# adc-breakout.net
KiCad netlist of a schematic drawn in Altium Designer
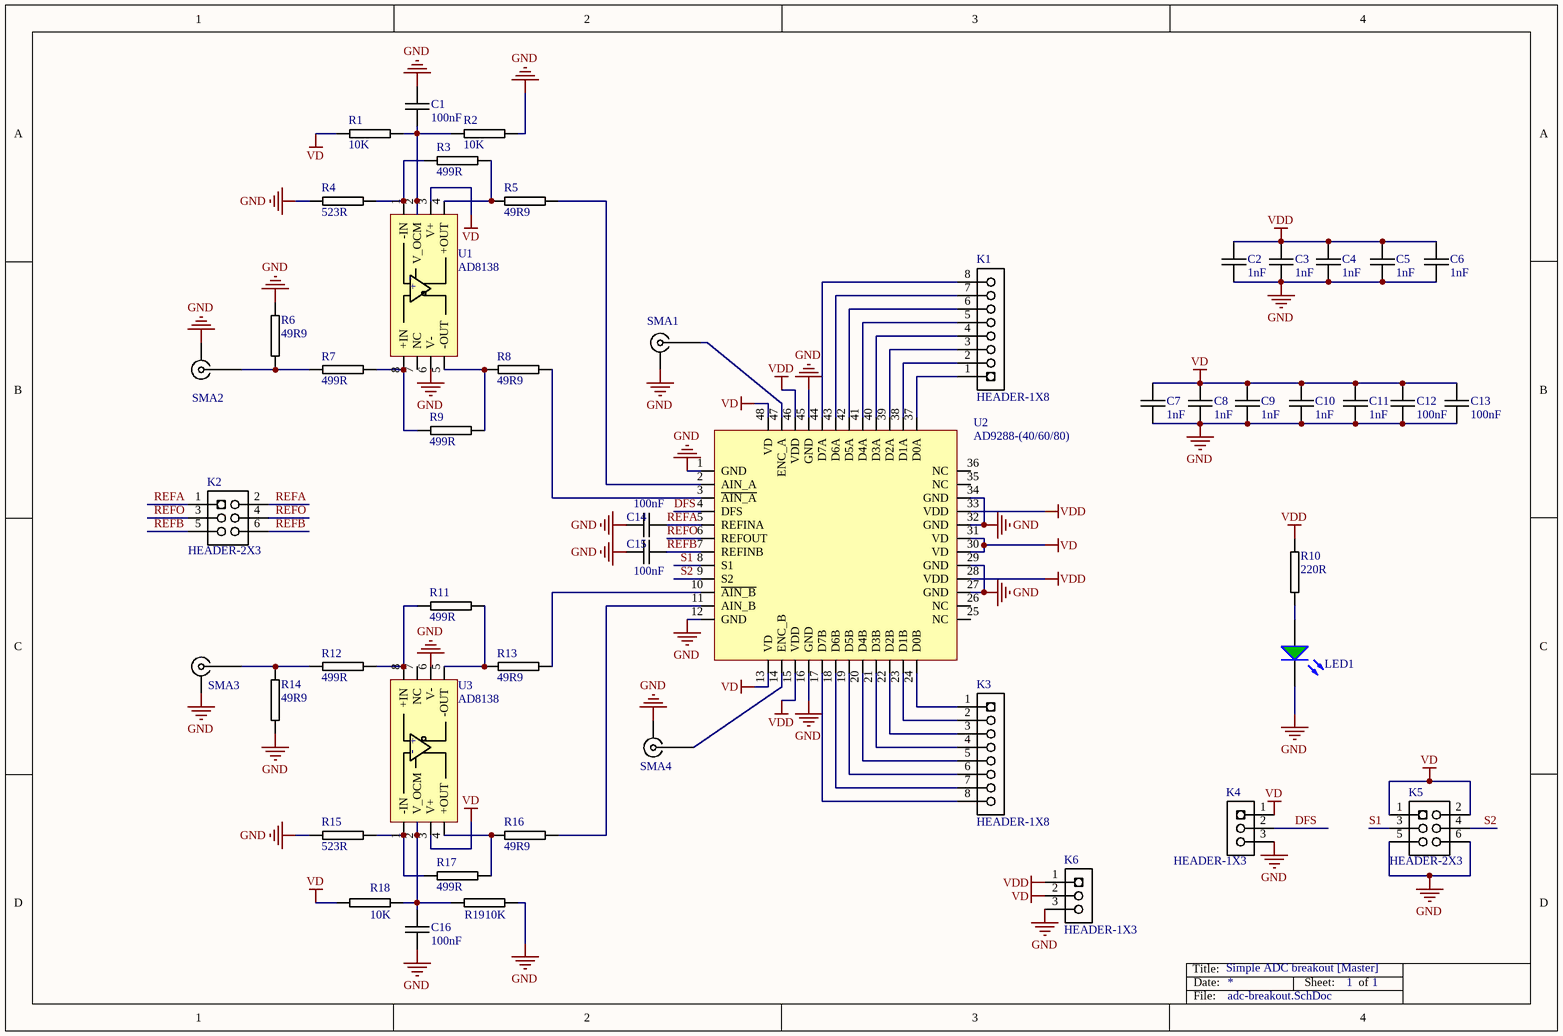
[diagram p0: adc-breakout.SchDoc]

(export (version "E")
  (design (tool "Eeschema 10.0.6"))
  (components
    (comp (ref "C1")
      (value "100nF")
      (footprint "0603C-GENERIC")
      (description "CAPACITOR 0603 CERAMIC")
      (fields
        (field (name "MANUFACTURER PART NUMBER") "C1608X7R1E104K")
        (field (name "MANUFACTURER") "TDK Corporation")
      )
      (libsource (lib "SMD Capacitors 0603") (part "0603C-100NF-25V-X7R-TDK"))
    )
    (comp (ref "C2")
      (value "1nF")
      (footprint "0603C-GENERIC")
      (description "CAPACITOR 0603 CERAMIC")
      (libsource (lib "SMD Capacitors 0603") (part "0603C-1NF-50V-X7R"))
    )
    (comp (ref "C3")
      (value "1nF")
      (footprint "0603C-GENERIC")
      (description "CAPACITOR 0603 CERAMIC")
      (libsource (lib "SMD Capacitors 0603") (part "0603C-1NF-50V-X7R"))
    )
    (comp (ref "C4")
      (value "1nF")
      (footprint "0603C-GENERIC")
      (description "CAPACITOR 0603 CERAMIC")
      (libsource (lib "SMD Capacitors 0603") (part "0603C-1NF-50V-X7R"))
    )
    (comp (ref "C5")
      (value "1nF")
      (footprint "0603C-GENERIC")
      (description "CAPACITOR 0603 CERAMIC")
      (libsource (lib "SMD Capacitors 0603") (part "0603C-1NF-50V-X7R"))
    )
    (comp (ref "C6")
      (value "1nF")
      (footprint "0603C-GENERIC")
      (description "CAPACITOR 0603 CERAMIC")
      (libsource (lib "SMD Capacitors 0603") (part "0603C-1NF-50V-X7R"))
    )
    (comp (ref "C7")
      (value "1nF")
      (footprint "0603C-GENERIC")
      (description "CAPACITOR 0603 CERAMIC")
      (libsource (lib "SMD Capacitors 0603") (part "0603C-1NF-50V-X7R"))
    )
    (comp (ref "C8")
      (value "1nF")
      (footprint "0603C-GENERIC")
      (description "CAPACITOR 0603 CERAMIC")
      (libsource (lib "SMD Capacitors 0603") (part "0603C-1NF-50V-X7R"))
    )
    (comp (ref "C9")
      (value "1nF")
      (footprint "0603C-GENERIC")
      (description "CAPACITOR 0603 CERAMIC")
      (libsource (lib "SMD Capacitors 0603") (part "0603C-1NF-50V-X7R"))
    )
    (comp (ref "C10")
      (value "1nF")
      (footprint "0603C-GENERIC")
      (description "CAPACITOR 0603 CERAMIC")
      (libsource (lib "SMD Capacitors 0603") (part "0603C-1NF-50V-X7R"))
    )
    (comp (ref "C11")
      (value "1nF")
      (footprint "0603C-GENERIC")
      (description "CAPACITOR 0603 CERAMIC")
      (libsource (lib "SMD Capacitors 0603") (part "0603C-1NF-50V-X7R"))
    )
    (comp (ref "C12")
      (value "100nF")
      (footprint "0603C-GENERIC")
      (description "CAPACITOR 0603 CERAMIC")
      (fields
        (field (name "MANUFACTURER PART NUMBER") "C1608X7R1E104K")
        (field (name "MANUFACTURER") "TDK Corporation")
      )
      (libsource (lib "SMD Capacitors 0603") (part "0603C-100NF-25V-X7R-TDK"))
    )
    (comp (ref "C13")
      (value "100nF")
      (footprint "0603C-GENERIC")
      (description "CAPACITOR 0603 CERAMIC")
      (fields
        (field (name "MANUFACTURER PART NUMBER") "C1608X7R1E104K")
        (field (name "MANUFACTURER") "TDK Corporation")
      )
      (libsource (lib "SMD Capacitors 0603") (part "0603C-100NF-25V-X7R-TDK"))
    )
    (comp (ref "C14")
      (value "100nF")
      (footprint "0603C-GENERIC")
      (description "CAPACITOR 0603 CERAMIC")
      (fields
        (field (name "MANUFACTURER PART NUMBER") "C1608X7R1E104K")
        (field (name "MANUFACTURER") "TDK Corporation")
      )
      (libsource (lib "SMD Capacitors 0603") (part "0603C-100NF-25V-X7R-TDK"))
    )
    (comp (ref "C15")
      (value "100nF")
      (footprint "0603C-GENERIC")
      (description "CAPACITOR 0603 CERAMIC")
      (fields
        (field (name "MANUFACTURER PART NUMBER") "C1608X7R1E104K")
        (field (name "MANUFACTURER") "TDK Corporation")
      )
      (libsource (lib "SMD Capacitors 0603") (part "0603C-100NF-25V-X7R-TDK"))
    )
    (comp (ref "C16")
      (value "100nF")
      (footprint "0603C-GENERIC")
      (description "CAPACITOR 0603 CERAMIC")
      (fields
        (field (name "MANUFACTURER PART NUMBER") "C1608X7R1E104K")
        (field (name "MANUFACTURER") "TDK Corporation")
      )
      (libsource (lib "SMD Capacitors 0603") (part "0603C-100NF-25V-X7R-TDK"))
    )
    (comp (ref "K1")
      (value "HEADER-1X8")
      (footprint "HEADER-1X8")
      (libsource (lib "TH Connectors") (part "HEADER-1X8"))
    )
    (comp (ref "K2")
      (value "HEADER-2X3")
      (footprint "HEADER-2X3")
      (libsource (lib "TH Connectors") (part "HEADER-2X3"))
    )
    (comp (ref "K3")
      (value "HEADER-1X8")
      (footprint "HEADER-1X8")
      (libsource (lib "TH Connectors") (part "HEADER-1X8"))
    )
    (comp (ref "K4")
      (value "HEADER-1X3")
      (footprint "HEADER-1X3")
      (libsource (lib "TH Connectors") (part "HEADER-1X3"))
    )
    (comp (ref "K5")
      (value "HEADER-2X3")
      (footprint "HEADER-2X3")
      (libsource (lib "TH Connectors") (part "HEADER-2X3"))
    )
    (comp (ref "K6")
      (value "HEADER-1X3")
      (footprint "HEADER-1X3")
      (libsource (lib "TH Connectors") (part "HEADER-1X3"))
    )
    (comp (ref "LED1")
      (value "Green")
      (footprint "0805LED - GREEN")
      (libsource (lib "custom_parts_old") (part "0805 SMD LED - GREEN"))
    )
    (comp (ref "R1")
      (value "10K")
      (footprint "0603R-10K")
      (description "GENERIC RESISTOR 0603")
      (fields (field (name "MANUFACTURER") "Stackpole Electronics Inc") (field (name "TOLERANCE") "±1%"))
      (libsource (lib "SMD Resistors 0603") (part "0603R-10K"))
    )
    (comp (ref "R2")
      (value "10K")
      (footprint "0603R-10K")
      (description "GENERIC RESISTOR 0603")
      (fields (field (name "MANUFACTURER") "Stackpole Electronics Inc") (field (name "TOLERANCE") "±1%"))
      (libsource (lib "SMD Resistors 0603") (part "0603R-10K"))
    )
    (comp (ref "R3")
      (value "499R")
      (footprint "0603R-GENERIC")
      (description "GENERIC RESISTOR 0603")
      (libsource (lib "SMD Resistors 0603") (part "0603R-499R"))
    )
    (comp (ref "R4")
      (value "523R")
      (footprint "0603R-GENERIC")
      (description "GENERIC RESISTOR 0603")
      (libsource (lib "SMD Resistors 0603") (part "0603R-499R"))
    )
    (comp (ref "R5")
      (value "49R9")
      (footprint "0603R-GENERIC")
      (description "GENERIC RESISTOR 0603")
      (libsource (lib "SMD Resistors 0603") (part "0603R-49R9"))
    )
    (comp (ref "R6")
      (value "49R9")
      (footprint "0603R-GENERIC")
      (description "GENERIC RESISTOR 0603")
      (libsource (lib "SMD Resistors 0603") (part "0603R-49R9"))
    )
    (comp (ref "R7")
      (value "499R")
      (footprint "0603R-GENERIC")
      (description "GENERIC RESISTOR 0603")
      (libsource (lib "SMD Resistors 0603") (part "0603R-499R"))
    )
    (comp (ref "R8")
      (value "49R9")
      (footprint "0603R-GENERIC")
      (description "GENERIC RESISTOR 0603")
      (libsource (lib "SMD Resistors 0603") (part "0603R-49R9"))
    )
    (comp (ref "R9")
      (value "499R")
      (footprint "0603R-GENERIC")
      (description "GENERIC RESISTOR 0603")
      (libsource (lib "SMD Resistors 0603") (part "0603R-499R"))
    )
    (comp (ref "R10")
      (value "220R")
      (footprint "0603R-220")
      (description "GENERIC RESISTOR 0603")
      (fields
        (field (name "MANUFACTURER") "Stackpole Electronics Inc")
        (field (name "MANUFACTURER PART NUMBER") "RMCF 1/16 220 1% R")
      )
      (libsource (lib "SMD Resistors 0603") (part "0603R-220"))
    )
    (comp (ref "R11")
      (value "499R")
      (footprint "0603R-GENERIC")
      (description "GENERIC RESISTOR 0603")
      (libsource (lib "SMD Resistors 0603") (part "0603R-499R"))
    )
    (comp (ref "R12")
      (value "499R")
      (footprint "0603R-GENERIC")
      (description "GENERIC RESISTOR 0603")
      (libsource (lib "SMD Resistors 0603") (part "0603R-499R"))
    )
    (comp (ref "R13")
      (value "49R9")
      (footprint "0603R-GENERIC")
      (description "GENERIC RESISTOR 0603")
      (libsource (lib "SMD Resistors 0603") (part "0603R-49R9"))
    )
    (comp (ref "R14")
      (value "49R9")
      (footprint "0603R-GENERIC")
      (description "GENERIC RESISTOR 0603")
      (libsource (lib "SMD Resistors 0603") (part "0603R-49R9"))
    )
    (comp (ref "R15")
      (value "523R")
      (footprint "0603R-GENERIC")
      (description "GENERIC RESISTOR 0603")
      (libsource (lib "SMD Resistors 0603") (part "0603R-499R"))
    )
    (comp (ref "R16")
      (value "49R9")
      (footprint "0603R-GENERIC")
      (description "GENERIC RESISTOR 0603")
      (libsource (lib "SMD Resistors 0603") (part "0603R-49R9"))
    )
    (comp (ref "R17")
      (value "499R")
      (footprint "0603R-GENERIC")
      (description "GENERIC RESISTOR 0603")
      (libsource (lib "SMD Resistors 0603") (part "0603R-499R"))
    )
    (comp (ref "R18")
      (value "10K")
      (footprint "0603R-10K")
      (description "GENERIC RESISTOR 0603")
      (fields (field (name "MANUFACTURER") "Stackpole Electronics Inc") (field (name "TOLERANCE") "±1%"))
      (libsource (lib "SMD Resistors 0603") (part "0603R-10K"))
    )
    (comp (ref "R19")
      (value "10K")
      (footprint "0603R-10K")
      (description "GENERIC RESISTOR 0603")
      (fields (field (name "MANUFACTURER") "Stackpole Electronics Inc") (field (name "TOLERANCE") "±1%"))
      (libsource (lib "SMD Resistors 0603") (part "0603R-10K"))
    )
    (comp (ref "SMA1")
      (value "*")
      (footprint "MOLEX_SMA_EDGE")
      (libsource (lib "") (part "MOLEX_SMA_EDGE_1"))
    )
    (comp (ref "SMA2")
      (value "*")
      (footprint "MOLEX_SMA_EDGE")
      (libsource (lib "rf_new") (part "MOLEX_SMA_EDGE"))
    )
    (comp (ref "SMA3")
      (value "*")
      (footprint "MOLEX_SMA_EDGE")
      (libsource (lib "") (part "MOLEX_SMA_EDGE_1"))
    )
    (comp (ref "SMA4")
      (value "*")
      (footprint "MOLEX_SMA_EDGE")
      (libsource (lib "rf_new") (part "MOLEX_SMA_EDGE"))
    )
    (comp (ref "U1") (value "AD8138") (footprint "AD8138-SOIC8") (libsource (lib "rf_new") (part "AD8138")))
    (comp (ref "U2")
      (value "AD9288-(40/60/80)")
      (footprint "ad9288-48QFP")
      (libsource (lib "rf_new") (part "AD9288"))
    )
    (comp (ref "U3") (value "AD8138") (footprint "AD8138-SOIC8") (libsource (lib "") (part "AD8138_1")))
  )
  (nets
    (net (code "1") (name "/DFS") (class "Default")
      (node (ref "K4") (pin "2") (pintype "passive"))
      (node (ref "U2") (pin "4") (pinfunction "DFS_4") (pintype "passive"))
    )
    (net (code "2") (name "/REFA") (class "Default")
      (node (ref "C14") (pin "2") (pintype "passive"))
      (node (ref "K2") (pin "1") (pintype "passive"))
      (node (ref "K2") (pin "2") (pintype "passive"))
      (node (ref "U2") (pin "5") (pinfunction "REFINA_5") (pintype "passive"))
    )
    (net (code "3") (name "/REFB") (class "Default")
      (node (ref "C15") (pin "2") (pintype "passive"))
      (node (ref "K2") (pin "5") (pintype "passive"))
      (node (ref "K2") (pin "6") (pintype "passive"))
      (node (ref "U2") (pin "7") (pinfunction "REFINB_7") (pintype "passive"))
    )
    (net (code "4") (name "/REFO") (class "Default")
      (node (ref "K2") (pin "3") (pintype "passive"))
      (node (ref "K2") (pin "4") (pintype "passive"))
      (node (ref "U2") (pin "6") (pinfunction "REFOUT_6") (pintype "passive"))
    )
    (net (code "5") (name "/S1") (class "Default")
      (node (ref "K5") (pin "3") (pintype "passive"))
      (node (ref "U2") (pin "8") (pinfunction "S1_8") (pintype "passive"))
    )
    (net (code "6") (name "/S2") (class "Default")
      (node (ref "K5") (pin "4") (pintype "passive"))
      (node (ref "U2") (pin "9") (pinfunction "S2_9") (pintype "passive"))
    )
    (net (code "7") (name "GND") (class "Default")
      (node (ref "C1") (pin "2") (pintype "passive"))
      (node (ref "C10") (pin "1") (pintype "passive"))
      (node (ref "C11") (pin "1") (pintype "passive"))
      (node (ref "C12") (pin "2") (pintype "passive"))
      (node (ref "C13") (pin "2") (pintype "passive"))
      (node (ref "C14") (pin "1") (pintype "passive"))
      (node (ref "C15") (pin "1") (pintype "passive"))
      (node (ref "C16") (pin "2") (pintype "passive"))
      (node (ref "C2") (pin "1") (pintype "passive"))
      (node (ref "C3") (pin "1") (pintype "passive"))
      (node (ref "C4") (pin "1") (pintype "passive"))
      (node (ref "C5") (pin "1") (pintype "passive"))
      (node (ref "C6") (pin "1") (pintype "passive"))
      (node (ref "C7") (pin "1") (pintype "passive"))
      (node (ref "C8") (pin "1") (pintype "passive"))
      (node (ref "C9") (pin "1") (pintype "passive"))
      (node (ref "K4") (pin "3") (pintype "passive"))
      (node (ref "K5") (pin "5") (pintype "passive"))
      (node (ref "K5") (pin "6") (pintype "passive"))
      (node (ref "K6") (pin "3") (pintype "passive"))
      (node (ref "LED1") (pin "K") (pinfunction "K_K") (pintype "passive"))
      (node (ref "R14") (pin "2") (pintype "passive"))
      (node (ref "R15") (pin "1") (pintype "passive"))
      (node (ref "R19") (pin "2") (pintype "passive"))
      (node (ref "R2") (pin "2") (pintype "passive"))
      (node (ref "R4") (pin "1") (pintype "passive"))
      (node (ref "R6") (pin "2") (pintype "passive"))
      (node (ref "SMA1") (pin "2") (pinfunction "2_2") (pintype "passive"))
      (node (ref "SMA2") (pin "2") (pinfunction "2_2") (pintype "passive"))
      (node (ref "SMA3") (pin "2") (pinfunction "2_2") (pintype "passive"))
      (node (ref "SMA4") (pin "2") (pinfunction "2_2") (pintype "passive"))
      (node (ref "U1") (pin "6") (pinfunction "V-_6") (pintype "passive"))
      (node (ref "U2") (pin "1") (pinfunction "GND_1") (pintype "passive"))
      (node (ref "U2") (pin "12") (pinfunction "GND_12") (pintype "passive"))
      (node (ref "U2") (pin "16") (pinfunction "GND_16") (pintype "passive"))
      (node (ref "U2") (pin "27") (pinfunction "GND_27") (pintype "passive"))
      (node (ref "U2") (pin "29") (pinfunction "GND_29") (pintype "passive"))
      (node (ref "U2") (pin "32") (pinfunction "GND_32") (pintype "passive"))
      (node (ref "U2") (pin "34") (pinfunction "GND_34") (pintype "passive"))
      (node (ref "U2") (pin "45") (pinfunction "GND_45") (pintype "passive"))
      (node (ref "U3") (pin "6") (pinfunction "V-_6") (pintype "passive"))
    )
    (net (code "8") (name "Net-(LED1-PadA)") (class "Default")
      (node (ref "LED1") (pin "A") (pinfunction "A_A") (pintype "passive"))
      (node (ref "R10") (pin "2") (pintype "passive"))
    )
    (net (code "9") (name "Net-(R6-Pad1)") (class "Default")
      (node (ref "R6") (pin "1") (pintype "passive"))
      (node (ref "R7") (pin "1") (pintype "passive"))
      (node (ref "SMA2") (pin "1") (pinfunction "1_1") (pintype "passive"))
    )
    (net (code "10") (name "Net-(R12-Pad1)") (class "Default")
      (node (ref "R12") (pin "1") (pintype "passive"))
      (node (ref "R14") (pin "1") (pintype "passive"))
      (node (ref "SMA3") (pin "1") (pinfunction "1_1") (pintype "passive"))
    )
    (net (code "11") (name "Net-(U1-+IN)") (class "Default")
      (node (ref "R7") (pin "2") (pintype "passive"))
      (node (ref "R9") (pin "1") (pintype "passive"))
      (node (ref "U1") (pin "8") (pinfunction "+IN_8") (pintype "passive"))
    )
    (net (code "12") (name "Net-(U1-+OUT)") (class "Default")
      (node (ref "R3") (pin "2") (pintype "passive"))
      (node (ref "R5") (pin "1") (pintype "passive"))
      (node (ref "U1") (pin "4") (pinfunction "+OUT_4") (pintype "passive"))
    )
    (net (code "13") (name "Net-(U1--IN)") (class "Default")
      (node (ref "R3") (pin "1") (pintype "passive"))
      (node (ref "R4") (pin "2") (pintype "passive"))
      (node (ref "U1") (pin "1") (pinfunction "-IN_1") (pintype "passive"))
    )
    (net (code "14") (name "Net-(U1--OUT)") (class "Default")
      (node (ref "R8") (pin "1") (pintype "passive"))
      (node (ref "R9") (pin "2") (pintype "passive"))
      (node (ref "U1") (pin "5") (pinfunction "-OUT_5") (pintype "passive"))
    )
    (net (code "15") (name "Net-(U1-V_OCM)") (class "Default")
      (node (ref "C1") (pin "1") (pintype "passive"))
      (node (ref "R1") (pin "2") (pintype "passive"))
      (node (ref "R2") (pin "1") (pintype "passive"))
      (node (ref "U1") (pin "2") (pinfunction "V_OCM_2") (pintype "passive"))
    )
    (net (code "16") (name "Net-(U2-AIN_A)") (class "Default")
      (node (ref "R5") (pin "2") (pintype "passive"))
      (node (ref "U2") (pin "2") (pinfunction "AIN_A_2") (pintype "passive"))
    )
    (net (code "17") (name "Net-(U2-AIN_B)") (class "Default")
      (node (ref "R16") (pin "2") (pintype "passive"))
      (node (ref "U2") (pin "11") (pinfunction "AIN_B_11") (pintype "passive"))
    )
    (net (code "18") (name "Net-(U2-D0A)") (class "Default")
      (node (ref "K1") (pin "1") (pintype "passive"))
      (node (ref "U2") (pin "37") (pinfunction "D0A_37") (pintype "passive"))
    )
    (net (code "19") (name "Net-(U2-D0B)") (class "Default")
      (node (ref "K3") (pin "1") (pintype "passive"))
      (node (ref "U2") (pin "24") (pinfunction "D0B_24") (pintype "passive"))
    )
    (net (code "20") (name "Net-(U2-D1A)") (class "Default")
      (node (ref "K1") (pin "2") (pintype "passive"))
      (node (ref "U2") (pin "38") (pinfunction "D1A_38") (pintype "passive"))
    )
    (net (code "21") (name "Net-(U2-D1B)") (class "Default")
      (node (ref "K3") (pin "2") (pintype "passive"))
      (node (ref "U2") (pin "23") (pinfunction "D1B_23") (pintype "passive"))
    )
    (net (code "22") (name "Net-(U2-D2A)") (class "Default")
      (node (ref "K1") (pin "3") (pintype "passive"))
      (node (ref "U2") (pin "39") (pinfunction "D2A_39") (pintype "passive"))
    )
    (net (code "23") (name "Net-(U2-D2B)") (class "Default")
      (node (ref "K3") (pin "3") (pintype "passive"))
      (node (ref "U2") (pin "22") (pinfunction "D2B_22") (pintype "passive"))
    )
    (net (code "24") (name "Net-(U2-D3A)") (class "Default")
      (node (ref "K1") (pin "4") (pintype "passive"))
      (node (ref "U2") (pin "40") (pinfunction "D3A_40") (pintype "passive"))
    )
    (net (code "25") (name "Net-(U2-D3B)") (class "Default")
      (node (ref "K3") (pin "4") (pintype "passive"))
      (node (ref "U2") (pin "21") (pinfunction "D3B_21") (pintype "passive"))
    )
    (net (code "26") (name "Net-(U2-D4A)") (class "Default")
      (node (ref "K1") (pin "5") (pintype "passive"))
      (node (ref "U2") (pin "41") (pinfunction "D4A_41") (pintype "passive"))
    )
    (net (code "27") (name "Net-(U2-D4B)") (class "Default")
      (node (ref "K3") (pin "5") (pintype "passive"))
      (node (ref "U2") (pin "20") (pinfunction "D4B_20") (pintype "passive"))
    )
    (net (code "28") (name "Net-(U2-D5A)") (class "Default")
      (node (ref "K1") (pin "6") (pintype "passive"))
      (node (ref "U2") (pin "42") (pinfunction "D5A_42") (pintype "passive"))
    )
    (net (code "29") (name "Net-(U2-D5B)") (class "Default")
      (node (ref "K3") (pin "6") (pintype "passive"))
      (node (ref "U2") (pin "19") (pinfunction "D5B_19") (pintype "passive"))
    )
    (net (code "30") (name "Net-(U2-D6A)") (class "Default")
      (node (ref "K1") (pin "7") (pintype "passive"))
      (node (ref "U2") (pin "43") (pinfunction "D6A_43") (pintype "passive"))
    )
    (net (code "31") (name "Net-(U2-D6B)") (class "Default")
      (node (ref "K3") (pin "7") (pintype "passive"))
      (node (ref "U2") (pin "18") (pinfunction "D6B_18") (pintype "passive"))
    )
    (net (code "32") (name "Net-(U2-D7A)") (class "Default")
      (node (ref "K1") (pin "8") (pintype "passive"))
      (node (ref "U2") (pin "44") (pinfunction "D7A_44") (pintype "passive"))
    )
    (net (code "33") (name "Net-(U2-D7B)") (class "Default")
      (node (ref "K3") (pin "8") (pintype "passive"))
      (node (ref "U2") (pin "17") (pinfunction "D7B_17") (pintype "passive"))
    )
    (net (code "34") (name "Net-(U2-ENC_A)") (class "Default")
      (node (ref "SMA1") (pin "1") (pinfunction "1_1") (pintype "passive"))
      (node (ref "U2") (pin "47") (pinfunction "ENC_A_47") (pintype "passive"))
    )
    (net (code "35") (name "Net-(U2-ENC_B)") (class "Default")
      (node (ref "SMA4") (pin "1") (pinfunction "1_1") (pintype "passive"))
      (node (ref "U2") (pin "14") (pinfunction "ENC_B_14") (pintype "passive"))
    )
    (net (code "36") (name "Net-(U2-~{AIN_A})") (class "Default")
      (node (ref "R8") (pin "2") (pintype "passive"))
      (node (ref "U2") (pin "3") (pinfunction "~{AIN_A}_3") (pintype "passive"))
    )
    (net (code "37") (name "Net-(U2-~{AIN_B})") (class "Default")
      (node (ref "R13") (pin "2") (pintype "passive"))
      (node (ref "U2") (pin "10") (pinfunction "~{AIN_B}_10") (pintype "passive"))
    )
    (net (code "38") (name "Net-(U3-+IN)") (class "Default")
      (node (ref "R11") (pin "1") (pintype "passive"))
      (node (ref "R12") (pin "2") (pintype "passive"))
      (node (ref "U3") (pin "8") (pinfunction "+IN_8") (pintype "passive"))
    )
    (net (code "39") (name "Net-(U3-+OUT)") (class "Default")
      (node (ref "R16") (pin "1") (pintype "passive"))
      (node (ref "R17") (pin "2") (pintype "passive"))
      (node (ref "U3") (pin "4") (pinfunction "+OUT_4") (pintype "passive"))
    )
    (net (code "40") (name "Net-(U3--IN)") (class "Default")
      (node (ref "R15") (pin "2") (pintype "passive"))
      (node (ref "R17") (pin "1") (pintype "passive"))
      (node (ref "U3") (pin "1") (pinfunction "-IN_1") (pintype "passive"))
    )
    (net (code "41") (name "Net-(U3--OUT)") (class "Default")
      (node (ref "R11") (pin "2") (pintype "passive"))
      (node (ref "R13") (pin "1") (pintype "passive"))
      (node (ref "U3") (pin "5") (pinfunction "-OUT_5") (pintype "passive"))
    )
    (net (code "42") (name "Net-(U3-V_OCM)") (class "Default")
      (node (ref "C16") (pin "1") (pintype "passive"))
      (node (ref "R18") (pin "2") (pintype "passive"))
      (node (ref "R19") (pin "1") (pintype "passive"))
      (node (ref "U3") (pin "2") (pinfunction "V_OCM_2") (pintype "passive"))
    )
    (net (code "43") (name "VD") (class "Default")
      (node (ref "C10") (pin "2") (pintype "passive"))
      (node (ref "C11") (pin "2") (pintype "passive"))
      (node (ref "C12") (pin "1") (pintype "passive"))
      (node (ref "C13") (pin "1") (pintype "passive"))
      (node (ref "C7") (pin "2") (pintype "passive"))
      (node (ref "C8") (pin "2") (pintype "passive"))
      (node (ref "C9") (pin "2") (pintype "passive"))
      (node (ref "K4") (pin "1") (pintype "passive"))
      (node (ref "K5") (pin "1") (pintype "passive"))
      (node (ref "K5") (pin "2") (pintype "passive"))
      (node (ref "K6") (pin "2") (pintype "passive"))
      (node (ref "R1") (pin "1") (pintype "passive"))
      (node (ref "R18") (pin "1") (pintype "passive"))
      (node (ref "U1") (pin "3") (pinfunction "V+_3") (pintype "passive"))
      (node (ref "U2") (pin "13") (pinfunction "VD_13") (pintype "passive"))
      (node (ref "U2") (pin "30") (pinfunction "VD_30") (pintype "passive"))
      (node (ref "U2") (pin "31") (pinfunction "VD_31") (pintype "passive"))
      (node (ref "U2") (pin "48") (pinfunction "VD_48") (pintype "passive"))
      (node (ref "U3") (pin "3") (pinfunction "V+_3") (pintype "passive"))
    )
    (net (code "44") (name "VDD") (class "Default")
      (node (ref "C2") (pin "2") (pintype "passive"))
      (node (ref "C3") (pin "2") (pintype "passive"))
      (node (ref "C4") (pin "2") (pintype "passive"))
      (node (ref "C5") (pin "2") (pintype "passive"))
      (node (ref "C6") (pin "2") (pintype "passive"))
      (node (ref "K6") (pin "1") (pintype "passive"))
      (node (ref "R10") (pin "1") (pintype "passive"))
      (node (ref "U2") (pin "15") (pinfunction "VDD_15") (pintype "passive"))
      (node (ref "U2") (pin "28") (pinfunction "VDD_28") (pintype "passive"))
      (node (ref "U2") (pin "33") (pinfunction "VDD_33") (pintype "passive"))
      (node (ref "U2") (pin "46") (pinfunction "VDD_46") (pintype "passive"))
    )
    (net (code "45") (name "unconnected-(U1-NC-Pad7)") (class "Default")
      (node (ref "U1") (pin "7") (pinfunction "NC_7") (pintype "passive"))
    )
    (net (code "46") (name "unconnected-(U2-NC-Pad25)") (class "Default")
      (node (ref "U2") (pin "25") (pinfunction "NC_25") (pintype "passive"))
    )
    (net (code "47") (name "unconnected-(U2-NC-Pad26)") (class "Default")
      (node (ref "U2") (pin "26") (pinfunction "NC_26") (pintype "passive"))
    )
    (net (code "48") (name "unconnected-(U2-NC-Pad35)") (class "Default")
      (node (ref "U2") (pin "35") (pinfunction "NC_35") (pintype "passive"))
    )
    (net (code "49") (name "unconnected-(U2-NC-Pad36)") (class "Default")
      (node (ref "U2") (pin "36") (pinfunction "NC_36") (pintype "passive"))
    )
    (net (code "50") (name "unconnected-(U3-NC-Pad7)") (class "Default")
      (node (ref "U3") (pin "7") (pinfunction "NC_7") (pintype "passive"))
    )
  )
)
